# De5.net
KiCad netlist of a schematic drawn in Altium Designer
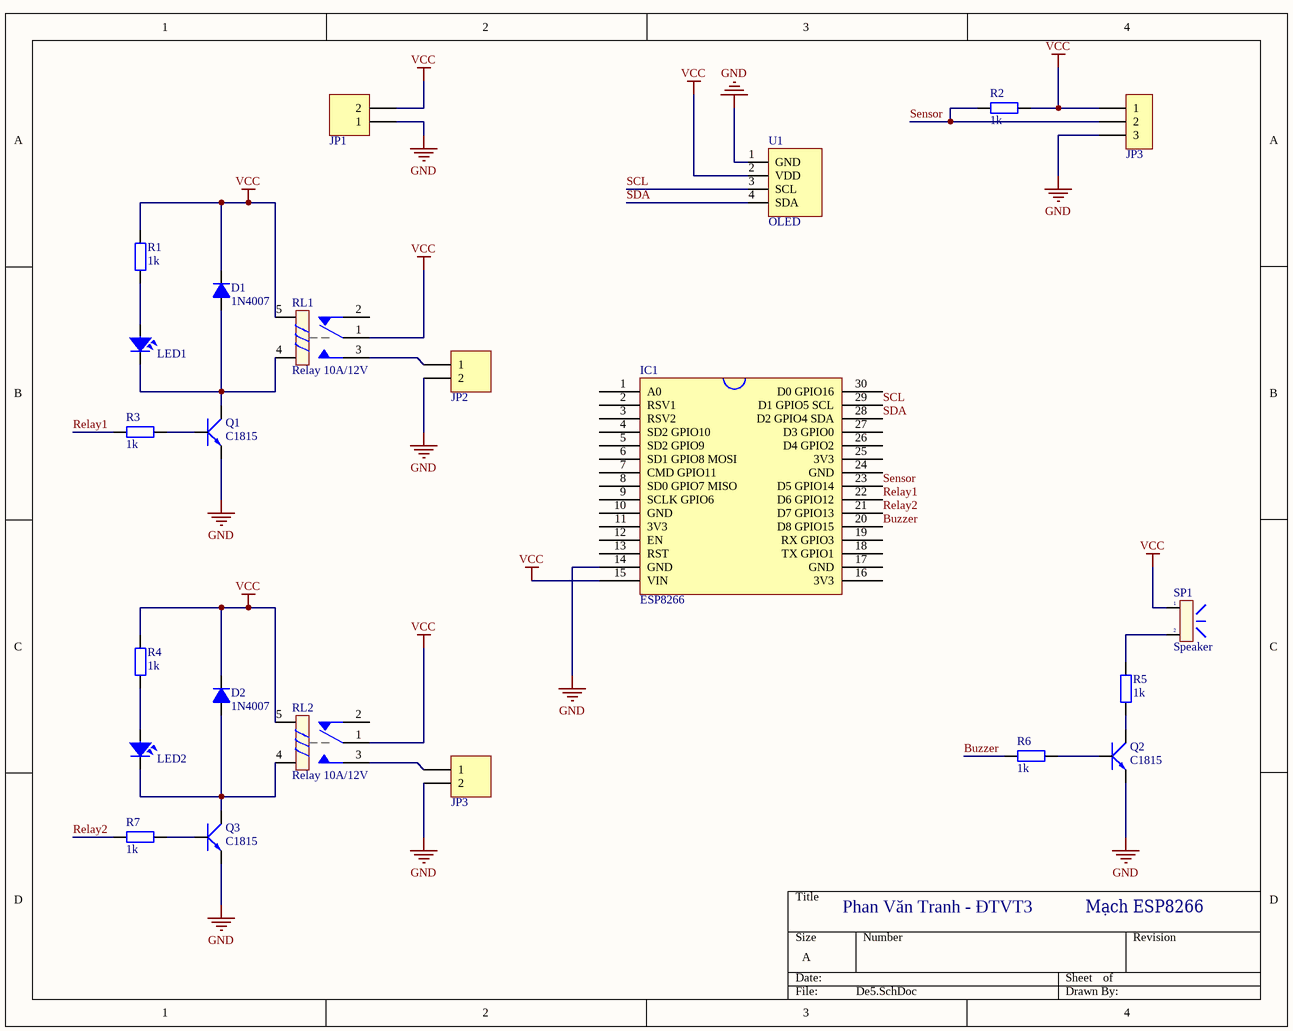
[diagram p0: De5.SchDoc]

(export (version "E")
  (design (tool "Eeschema 10.0.6"))
  (components
    (comp (ref "D1")
      (value "1N4007")
      (footprint "D1A")
      (description "Diode 1A")
      (libsource (lib "syhaunguyen") (part "D1A"))
    )
    (comp (ref "D2")
      (value "1N4007")
      (footprint "D1A")
      (description "Diode 1A")
      (libsource (lib "syhaunguyen") (part "D1A"))
    )
    (comp (ref "DHT11")
      (value "JP3")
      (footprint "Header 3P DC 2.54")
      (description "Cắm")
      (libsource (lib "Header") (part "Header 3P 2.54 Duc Cong"))
    )
    (comp (ref "IC1")
      (value "ESP8266")
      (footprint "ESP8266 - duplicate")
      (libsource (lib "ESP8266") (part "ESP8266"))
    )
    (comp (ref "JP1")
      (value "Header 2_1")
      (footprint "HED2")
      (description "Header, 2-Pin")
      (fields (field (name "MANUFACTURER") "Generic Components"))
      (libsource (lib "") (part "Header 2_1_1"))
    )
    (comp (ref "JP2")
      (value "Header 2_1")
      (footprint "HED2")
      (description "Header, 2-Pin")
      (fields (field (name "MANUFACTURER") "Generic Components"))
      (libsource (lib "syhaunguyen") (part "Header 2_1"))
    )
    (comp (ref "JP3")
      (value "Header 2_1")
      (footprint "HED2")
      (description "Header, 2-Pin")
      (fields (field (name "MANUFACTURER") "Generic Components"))
      (libsource (lib "syhaunguyen") (part "Header 2_1"))
    )
    (comp (ref "LED1")
      (value "LED")
      (footprint "LED-3")
      (description "LED Single colour Green and Red")
      (libsource (lib "syhaunguyen") (part "LED"))
    )
    (comp (ref "LED2")
      (value "LED")
      (footprint "LED-3")
      (description "LED Single colour Green and Red")
      (libsource (lib "syhaunguyen") (part "LED"))
    )
    (comp (ref "Q1")
      (value "C1815")
      (footprint "TO92")
      (description "NPN transistor")
      (libsource (lib "TranFet") (part "Trans C1815 DIP"))
    )
    (comp (ref "Q2")
      (value "C1815")
      (footprint "TO92")
      (description "NPN transistor")
      (libsource (lib "TranFet") (part "Trans C1815 DIP"))
    )
    (comp (ref "Q3")
      (value "C1815")
      (footprint "TO92")
      (description "NPN transistor")
      (libsource (lib "TranFet") (part "Trans C1815 DIP"))
    )
    (comp (ref "R1")
      (value "1k")
      (footprint "tro vach 1/4w")
      (description "Cắm")
      (libsource (lib "Resistor") (part "Tro Vach 1/4W 5% 1k"))
    )
    (comp (ref "R2")
      (value "1k")
      (footprint "tro vach 1/4w")
      (description "Cắm")
      (libsource (lib "Resistor") (part "Tro Vach 1/4W 5% 1k"))
    )
    (comp (ref "R3")
      (value "1k")
      (footprint "tro vach 1/4w")
      (description "Cắm")
      (libsource (lib "Resistor") (part "Tro Vach 1/4W 5% 1k"))
    )
    (comp (ref "R4")
      (value "1k")
      (footprint "tro vach 1/4w")
      (description "Cắm")
      (libsource (lib "Resistor") (part "Tro Vach 1/4W 5% 1k"))
    )
    (comp (ref "R5")
      (value "1k")
      (footprint "tro vach 1/4w")
      (description "Cắm")
      (libsource (lib "Resistor") (part "Tro Vach 1/4W 5% 1k"))
    )
    (comp (ref "R6")
      (value "1k")
      (footprint "tro vach 1/4w")
      (description "Cắm")
      (libsource (lib "Resistor") (part "Tro Vach 1/4W 5% 1k"))
    )
    (comp (ref "R7")
      (value "1k")
      (footprint "tro vach 1/4w")
      (description "Cắm")
      (libsource (lib "Resistor") (part "Tro Vach 1/4W 5% 1k"))
    )
    (comp (ref "RL1")
      (value "Relay 10A/12V")
      (footprint "RL_SPDT_10A")
      (description "Relay SPDT,10A - 12VDC 5 Pin")
      (libsource (lib "syhaunguyen") (part "Relay 1"))
    )
    (comp (ref "RL2")
      (value "Relay 10A/12V")
      (footprint "RL_SPDT_10A")
      (description "Relay SPDT,10A - 12VDC 5 Pin")
      (libsource (lib "syhaunguyen") (part "Relay 1"))
    )
    (comp (ref "SP1")
      (value "Speaker")
      (footprint "SPK")
      (description "Speaker Chip")
      (libsource (lib "syhaunguyen") (part "SPK"))
    )
    (comp (ref "U1") (value "OLED") (footprint "OLED1306") (libsource (lib "OLED1306") (part "OLED1306")))
  )
  (nets
    (net (code "1") (name "/Buzzer") (class "Default")
      (node (ref "IC1") (pin "20") (pinfunction "D8_GPIO15_20") (pintype "passive"))
      (node (ref "R6") (pin "1") (pinfunction "1_1") (pintype "passive"))
    )
    (net (code "2") (name "/Relay1") (class "Default")
      (node (ref "IC1") (pin "22") (pinfunction "D6_GPIO12_22") (pintype "passive"))
      (node (ref "R3") (pin "1") (pinfunction "1_1") (pintype "passive"))
    )
    (net (code "3") (name "/Relay2") (class "Default")
      (node (ref "IC1") (pin "21") (pinfunction "D7_GPIO13_21") (pintype "passive"))
      (node (ref "R7") (pin "1") (pinfunction "1_1") (pintype "passive"))
    )
    (net (code "4") (name "/SCL") (class "Default")
      (node (ref "IC1") (pin "29") (pinfunction "D1_GPIO5_SCL_29") (pintype "passive"))
      (node (ref "U1") (pin "3") (pinfunction "SCL_3") (pintype "passive"))
    )
    (net (code "5") (name "/SDA") (class "Default")
      (node (ref "IC1") (pin "28") (pinfunction "D2_GPIO4_SDA_28") (pintype "passive"))
      (node (ref "U1") (pin "4") (pinfunction "SDA_4") (pintype "passive"))
    )
    (net (code "6") (name "/Sensor") (class "Default")
      (node (ref "DHT11") (pin "2") (pinfunction "2_2") (pintype "passive"))
      (node (ref "IC1") (pin "23") (pinfunction "D5_GPIO14_23") (pintype "passive"))
      (node (ref "R2") (pin "1") (pinfunction "1_1") (pintype "passive"))
    )
    (net (code "7") (name "GND") (class "Default")
      (node (ref "DHT11") (pin "3") (pinfunction "3_3") (pintype "passive"))
      (node (ref "IC1") (pin "14") (pinfunction "GND_14") (pintype "passive"))
      (node (ref "JP1") (pin "1") (pinfunction "1_1") (pintype "passive"))
      (node (ref "JP2") (pin "2") (pinfunction "2_2") (pintype "passive"))
      (node (ref "JP3") (pin "2") (pinfunction "2_2") (pintype "passive"))
      (node (ref "Q1") (pin "1") (pinfunction "E_1") (pintype "passive"))
      (node (ref "Q2") (pin "1") (pinfunction "E_1") (pintype "passive"))
      (node (ref "Q3") (pin "1") (pinfunction "E_1") (pintype "passive"))
      (node (ref "U1") (pin "1") (pinfunction "GND_1") (pintype "passive"))
    )
    (net (code "8") (name "Net-(D1-A)") (class "Default")
      (node (ref "D1") (pin "1") (pinfunction "A_1") (pintype "passive"))
      (node (ref "LED1") (pin "2") (pinfunction "2_2") (pintype "passive"))
      (node (ref "Q1") (pin "2") (pinfunction "C_2") (pintype "passive"))
      (node (ref "RL1") (pin "4") (pinfunction "4_4") (pintype "passive"))
    )
    (net (code "9") (name "Net-(D2-A)") (class "Default")
      (node (ref "D2") (pin "1") (pinfunction "A_1") (pintype "passive"))
      (node (ref "LED2") (pin "2") (pinfunction "2_2") (pintype "passive"))
      (node (ref "Q3") (pin "2") (pinfunction "C_2") (pintype "passive"))
      (node (ref "RL2") (pin "4") (pinfunction "4_4") (pintype "passive"))
    )
    (net (code "10") (name "Net-(JP2-Pad1)") (class "Default")
      (node (ref "JP2") (pin "1") (pinfunction "1_1") (pintype "passive"))
      (node (ref "RL1") (pin "3") (pinfunction "3_3") (pintype "passive"))
    )
    (net (code "11") (name "Net-(JP3-Pad1)") (class "Default")
      (node (ref "JP3") (pin "1") (pinfunction "1_1") (pintype "passive"))
      (node (ref "RL2") (pin "3") (pinfunction "3_3") (pintype "passive"))
    )
    (net (code "12") (name "Net-(LED1-Pad1)") (class "Default")
      (node (ref "LED1") (pin "1") (pinfunction "1_1") (pintype "passive"))
      (node (ref "R1") (pin "2") (pinfunction "2_2") (pintype "passive"))
    )
    (net (code "13") (name "Net-(LED2-Pad1)") (class "Default")
      (node (ref "LED2") (pin "1") (pinfunction "1_1") (pintype "passive"))
      (node (ref "R4") (pin "2") (pinfunction "2_2") (pintype "passive"))
    )
    (net (code "14") (name "Net-(Q1-B)") (class "Default")
      (node (ref "Q1") (pin "3") (pinfunction "B_3") (pintype "passive"))
      (node (ref "R3") (pin "2") (pinfunction "2_2") (pintype "passive"))
    )
    (net (code "15") (name "Net-(Q2-B)") (class "Default")
      (node (ref "Q2") (pin "3") (pinfunction "B_3") (pintype "passive"))
      (node (ref "R6") (pin "2") (pinfunction "2_2") (pintype "passive"))
    )
    (net (code "16") (name "Net-(Q2-C)") (class "Default")
      (node (ref "Q2") (pin "2") (pinfunction "C_2") (pintype "passive"))
      (node (ref "R5") (pin "2") (pinfunction "2_2") (pintype "passive"))
    )
    (net (code "17") (name "Net-(Q3-B)") (class "Default")
      (node (ref "Q3") (pin "3") (pinfunction "B_3") (pintype "passive"))
      (node (ref "R7") (pin "2") (pinfunction "2_2") (pintype "passive"))
    )
    (net (code "18") (name "Net-(R5-Pad1)") (class "Default")
      (node (ref "R5") (pin "1") (pinfunction "1_1") (pintype "passive"))
      (node (ref "SP1") (pin "2") (pinfunction "2_2") (pintype "passive"))
    )
    (net (code "19") (name "VCC") (class "Default")
      (node (ref "D1") (pin "2") (pinfunction "K_2") (pintype "passive"))
      (node (ref "D2") (pin "2") (pinfunction "K_2") (pintype "passive"))
      (node (ref "DHT11") (pin "1") (pinfunction "1_1") (pintype "passive"))
      (node (ref "IC1") (pin "15") (pinfunction "VIN_15") (pintype "passive"))
      (node (ref "JP1") (pin "2") (pinfunction "2_2") (pintype "passive"))
      (node (ref "R1") (pin "1") (pinfunction "1_1") (pintype "passive"))
      (node (ref "R2") (pin "2") (pinfunction "2_2") (pintype "passive"))
      (node (ref "R4") (pin "1") (pinfunction "1_1") (pintype "passive"))
      (node (ref "RL1") (pin "1") (pinfunction "1_1") (pintype "passive"))
      (node (ref "RL1") (pin "5") (pinfunction "5_5") (pintype "passive"))
      (node (ref "RL2") (pin "1") (pinfunction "1_1") (pintype "passive"))
      (node (ref "RL2") (pin "5") (pinfunction "5_5") (pintype "passive"))
      (node (ref "SP1") (pin "1") (pinfunction "1_1") (pintype "passive"))
      (node (ref "U1") (pin "2") (pinfunction "VDD_2") (pintype "passive"))
    )
    (net (code "20") (name "unconnected-(IC1-3V3-Pad11)") (class "Default")
      (node (ref "IC1") (pin "11") (pinfunction "3V3_11") (pintype "passive"))
    )
    (net (code "21") (name "unconnected-(IC1-3V3-Pad16)") (class "Default")
      (node (ref "IC1") (pin "16") (pinfunction "3V3_16") (pintype "passive"))
    )
    (net (code "22") (name "unconnected-(IC1-3V3-Pad25)") (class "Default")
      (node (ref "IC1") (pin "25") (pinfunction "3V3_25") (pintype "passive"))
    )
    (net (code "23") (name "unconnected-(IC1-A0-Pad1)") (class "Default")
      (node (ref "IC1") (pin "1") (pinfunction "A0_1") (pintype "passive"))
    )
    (net (code "24") (name "unconnected-(IC1-CMD_GPIO11-Pad7)") (class "Default")
      (node (ref "IC1") (pin "7") (pinfunction "CMD_GPIO11_7") (pintype "passive"))
    )
    (net (code "25") (name "unconnected-(IC1-D0_GPIO16-Pad30)") (class "Default")
      (node (ref "IC1") (pin "30") (pinfunction "D0_GPIO16_30") (pintype "passive"))
    )
    (net (code "26") (name "unconnected-(IC1-D3_GPIO0-Pad27)") (class "Default")
      (node (ref "IC1") (pin "27") (pinfunction "D3_GPIO0_27") (pintype "passive"))
    )
    (net (code "27") (name "unconnected-(IC1-D4_GPIO2-Pad26)") (class "Default")
      (node (ref "IC1") (pin "26") (pinfunction "D4_GPIO2_26") (pintype "passive"))
    )
    (net (code "28") (name "unconnected-(IC1-EN-Pad12)") (class "Default")
      (node (ref "IC1") (pin "12") (pinfunction "EN_12") (pintype "passive"))
    )
    (net (code "29") (name "unconnected-(IC1-GND-Pad10)") (class "Default")
      (node (ref "IC1") (pin "10") (pinfunction "GND_10") (pintype "passive"))
    )
    (net (code "30") (name "unconnected-(IC1-GND-Pad17)") (class "Default")
      (node (ref "IC1") (pin "17") (pinfunction "GND_17") (pintype "passive"))
    )
    (net (code "31") (name "unconnected-(IC1-GND-Pad24)") (class "Default")
      (node (ref "IC1") (pin "24") (pinfunction "GND_24") (pintype "passive"))
    )
    (net (code "32") (name "unconnected-(IC1-RST-Pad13)") (class "Default")
      (node (ref "IC1") (pin "13") (pinfunction "RST_13") (pintype "passive"))
    )
    (net (code "33") (name "unconnected-(IC1-RSV1-Pad2)") (class "Default")
      (node (ref "IC1") (pin "2") (pinfunction "RSV1_2") (pintype "passive"))
    )
    (net (code "34") (name "unconnected-(IC1-RSV2-Pad3)") (class "Default")
      (node (ref "IC1") (pin "3") (pinfunction "RSV2_3") (pintype "passive"))
    )
    (net (code "35") (name "unconnected-(IC1-RX_GPIO3-Pad19)") (class "Default")
      (node (ref "IC1") (pin "19") (pinfunction "RX_GPIO3_19") (pintype "passive"))
    )
    (net (code "36") (name "unconnected-(IC1-SCLK_GPIO6-Pad9)") (class "Default")
      (node (ref "IC1") (pin "9") (pinfunction "SCLK_GPIO6_9") (pintype "passive"))
    )
    (net (code "37") (name "unconnected-(IC1-SD0_GPIO7_MISO-Pad8)") (class "Default")
      (node (ref "IC1") (pin "8") (pinfunction "SD0_GPIO7_MISO_8") (pintype "passive"))
    )
    (net (code "38") (name "unconnected-(IC1-SD1_GPIO8_MOSI-Pad6)") (class "Default")
      (node (ref "IC1") (pin "6") (pinfunction "SD1_GPIO8_MOSI_6") (pintype "passive"))
    )
    (net (code "39") (name "unconnected-(IC1-SD2_GPIO9-Pad5)") (class "Default")
      (node (ref "IC1") (pin "5") (pinfunction "SD2_GPIO9_5") (pintype "passive"))
    )
    (net (code "40") (name "unconnected-(IC1-SD2_GPIO10-Pad4)") (class "Default")
      (node (ref "IC1") (pin "4") (pinfunction "SD2_GPIO10_4") (pintype "passive"))
    )
    (net (code "41") (name "unconnected-(IC1-TX_GPIO1-Pad18)") (class "Default")
      (node (ref "IC1") (pin "18") (pinfunction "TX_GPIO1_18") (pintype "passive"))
    )
    (net (code "42") (name "unconnected-(RL1-Pad2)") (class "Default")
      (node (ref "RL1") (pin "2") (pinfunction "2_2") (pintype "passive"))
    )
    (net (code "43") (name "unconnected-(RL2-Pad2)") (class "Default")
      (node (ref "RL2") (pin "2") (pinfunction "2_2") (pintype "passive"))
    )
  )
)
